# Sheet1.net
KiCad netlist of a schematic drawn in Altium Designer
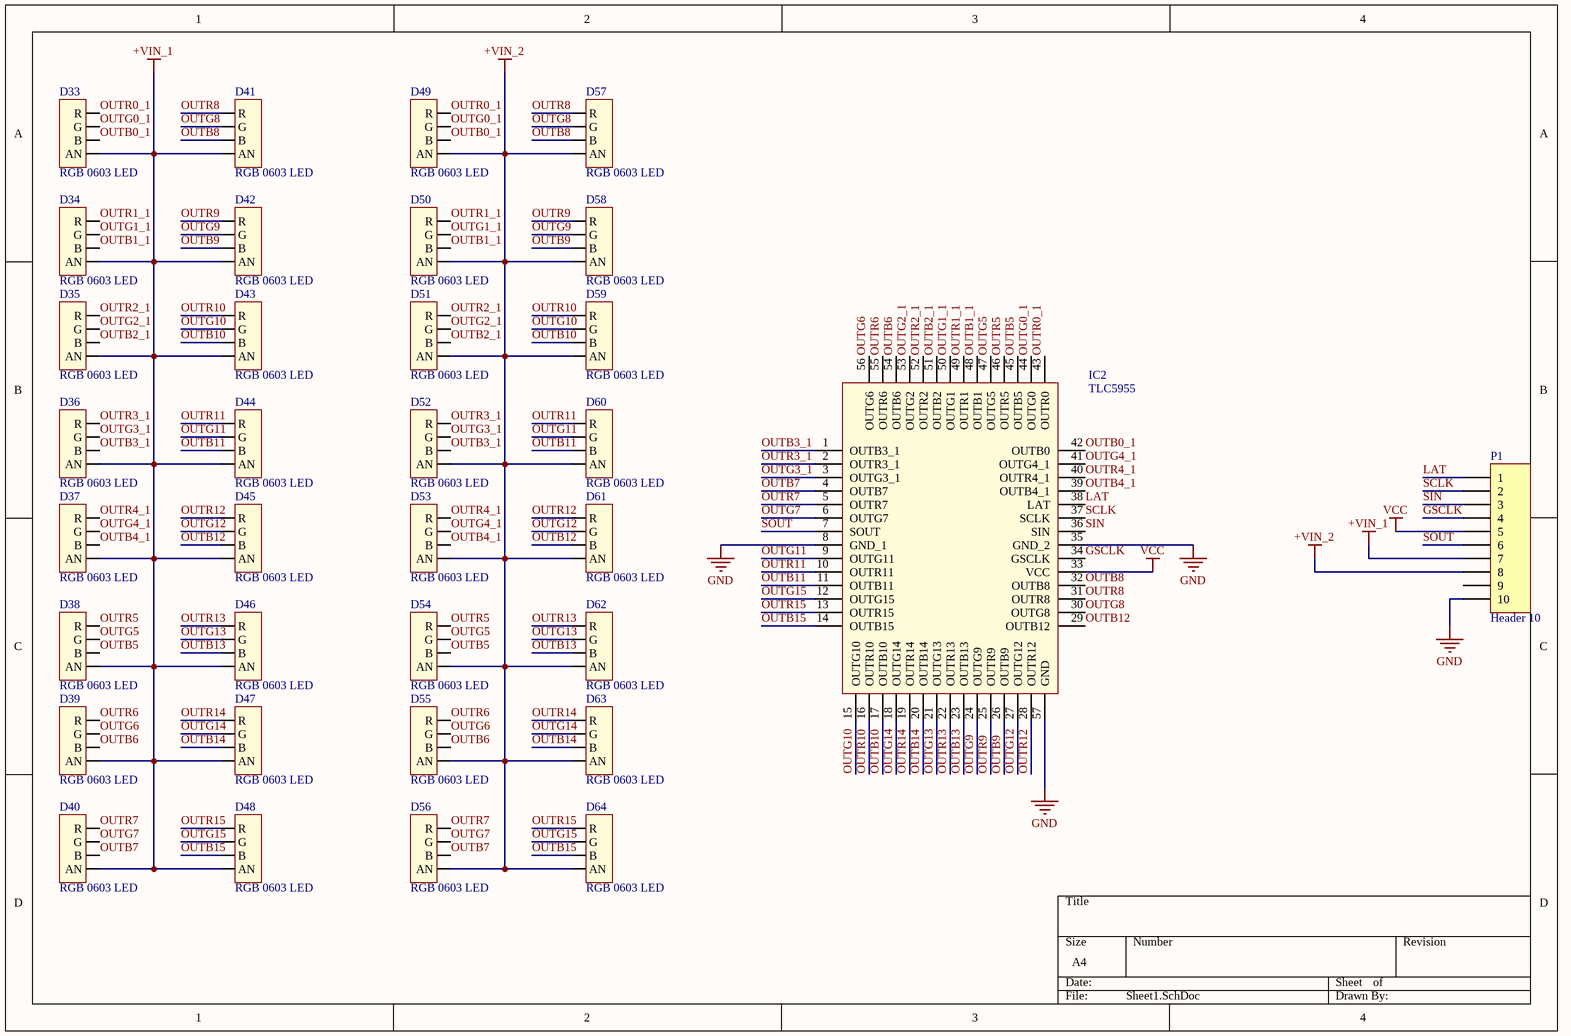
[diagram p0: Sheet1.SchDoc]

(export (version "E")
  (design (tool "Eeschema 10.0.6"))
  (components
    (comp (ref "D33")
      (value "RGB 0603 LED")
      (footprint "RGB LED")
      (libsource (lib "Schlib1") (part "RGB 0603 LED"))
    )
    (comp (ref "D34")
      (value "RGB 0603 LED")
      (footprint "RGB LED")
      (libsource (lib "Schlib1") (part "RGB 0603 LED"))
    )
    (comp (ref "D35")
      (value "RGB 0603 LED")
      (footprint "RGB LED")
      (libsource (lib "Schlib1") (part "RGB 0603 LED"))
    )
    (comp (ref "D36")
      (value "RGB 0603 LED")
      (footprint "RGB LED")
      (libsource (lib "Schlib1") (part "RGB 0603 LED"))
    )
    (comp (ref "D37")
      (value "RGB 0603 LED")
      (footprint "RGB LED")
      (libsource (lib "Schlib1") (part "RGB 0603 LED"))
    )
    (comp (ref "D38")
      (value "RGB 0603 LED")
      (footprint "RGB LED")
      (libsource (lib "Schlib1") (part "RGB 0603 LED"))
    )
    (comp (ref "D39")
      (value "RGB 0603 LED")
      (footprint "RGB LED")
      (libsource (lib "Schlib1") (part "RGB 0603 LED"))
    )
    (comp (ref "D40")
      (value "RGB 0603 LED")
      (footprint "RGB LED")
      (libsource (lib "Schlib1") (part "RGB 0603 LED"))
    )
    (comp (ref "D41")
      (value "RGB 0603 LED")
      (footprint "RGB LED")
      (libsource (lib "") (part "RGB 0603 LED_1"))
    )
    (comp (ref "D42")
      (value "RGB 0603 LED")
      (footprint "RGB LED")
      (libsource (lib "") (part "RGB 0603 LED_1"))
    )
    (comp (ref "D43")
      (value "RGB 0603 LED")
      (footprint "RGB LED")
      (libsource (lib "") (part "RGB 0603 LED_1"))
    )
    (comp (ref "D44")
      (value "RGB 0603 LED")
      (footprint "RGB LED")
      (libsource (lib "") (part "RGB 0603 LED_1"))
    )
    (comp (ref "D45")
      (value "RGB 0603 LED")
      (footprint "RGB LED")
      (libsource (lib "") (part "RGB 0603 LED_1"))
    )
    (comp (ref "D46")
      (value "RGB 0603 LED")
      (footprint "RGB LED")
      (libsource (lib "") (part "RGB 0603 LED_1"))
    )
    (comp (ref "D47")
      (value "RGB 0603 LED")
      (footprint "RGB LED")
      (libsource (lib "") (part "RGB 0603 LED_1"))
    )
    (comp (ref "D48")
      (value "RGB 0603 LED")
      (footprint "RGB LED")
      (libsource (lib "") (part "RGB 0603 LED_1"))
    )
    (comp (ref "D49")
      (value "RGB 0603 LED")
      (footprint "RGB LED")
      (libsource (lib "Schlib1") (part "RGB 0603 LED"))
    )
    (comp (ref "D50")
      (value "RGB 0603 LED")
      (footprint "RGB LED")
      (libsource (lib "Schlib1") (part "RGB 0603 LED"))
    )
    (comp (ref "D51")
      (value "RGB 0603 LED")
      (footprint "RGB LED")
      (libsource (lib "Schlib1") (part "RGB 0603 LED"))
    )
    (comp (ref "D52")
      (value "RGB 0603 LED")
      (footprint "RGB LED")
      (libsource (lib "Schlib1") (part "RGB 0603 LED"))
    )
    (comp (ref "D53")
      (value "RGB 0603 LED")
      (footprint "RGB LED")
      (libsource (lib "Schlib1") (part "RGB 0603 LED"))
    )
    (comp (ref "D54")
      (value "RGB 0603 LED")
      (footprint "RGB LED")
      (libsource (lib "Schlib1") (part "RGB 0603 LED"))
    )
    (comp (ref "D55")
      (value "RGB 0603 LED")
      (footprint "RGB LED")
      (libsource (lib "Schlib1") (part "RGB 0603 LED"))
    )
    (comp (ref "D56")
      (value "RGB 0603 LED")
      (footprint "RGB LED")
      (libsource (lib "Schlib1") (part "RGB 0603 LED"))
    )
    (comp (ref "D57")
      (value "RGB 0603 LED")
      (footprint "RGB LED")
      (libsource (lib "") (part "RGB 0603 LED_1"))
    )
    (comp (ref "D58")
      (value "RGB 0603 LED")
      (footprint "RGB LED")
      (libsource (lib "") (part "RGB 0603 LED_1"))
    )
    (comp (ref "D59")
      (value "RGB 0603 LED")
      (footprint "RGB LED")
      (libsource (lib "") (part "RGB 0603 LED_1"))
    )
    (comp (ref "D60")
      (value "RGB 0603 LED")
      (footprint "RGB LED")
      (libsource (lib "") (part "RGB 0603 LED_1"))
    )
    (comp (ref "D61")
      (value "RGB 0603 LED")
      (footprint "RGB LED")
      (libsource (lib "") (part "RGB 0603 LED_1"))
    )
    (comp (ref "D62")
      (value "RGB 0603 LED")
      (footprint "RGB LED")
      (libsource (lib "") (part "RGB 0603 LED_1"))
    )
    (comp (ref "D63")
      (value "RGB 0603 LED")
      (footprint "RGB LED")
      (libsource (lib "") (part "RGB 0603 LED_1"))
    )
    (comp (ref "D64")
      (value "RGB 0603 LED")
      (footprint "RGB LED")
      (libsource (lib "") (part "RGB 0603 LED_1"))
    )
    (comp (ref "IC2") (value "TLC5955") (footprint "TLC5955") (libsource (lib "Schlib1") (part "TLC5955")))
    (comp (ref "P1")
      (value "Header 10")
      (footprint "HDR1X10")
      (description "Header, 10-Pin")
      (fields (field (name "PUBLISHER") "Altium Limited"))
      (libsource (lib "Miscellaneous Connectors") (part "Header 10"))
    )
  )
  (nets
    (net (code "1") (name "+VIN_1") (class "Default")
      (node (ref "D33") (pin "4") (pinfunction "AN_4") (pintype "passive"))
      (node (ref "D34") (pin "4") (pinfunction "AN_4") (pintype "passive"))
      (node (ref "D35") (pin "4") (pinfunction "AN_4") (pintype "passive"))
      (node (ref "D36") (pin "4") (pinfunction "AN_4") (pintype "passive"))
      (node (ref "D37") (pin "4") (pinfunction "AN_4") (pintype "passive"))
      (node (ref "D38") (pin "4") (pinfunction "AN_4") (pintype "passive"))
      (node (ref "D39") (pin "4") (pinfunction "AN_4") (pintype "passive"))
      (node (ref "D40") (pin "4") (pinfunction "AN_4") (pintype "passive"))
      (node (ref "D41") (pin "4") (pinfunction "AN_4") (pintype "passive"))
      (node (ref "D42") (pin "4") (pinfunction "AN_4") (pintype "passive"))
      (node (ref "D43") (pin "4") (pinfunction "AN_4") (pintype "passive"))
      (node (ref "D44") (pin "4") (pinfunction "AN_4") (pintype "passive"))
      (node (ref "D45") (pin "4") (pinfunction "AN_4") (pintype "passive"))
      (node (ref "D46") (pin "4") (pinfunction "AN_4") (pintype "passive"))
      (node (ref "D47") (pin "4") (pinfunction "AN_4") (pintype "passive"))
      (node (ref "D48") (pin "4") (pinfunction "AN_4") (pintype "passive"))
      (node (ref "P1") (pin "7") (pinfunction "7_7") (pintype "passive"))
    )
    (net (code "2") (name "+VIN_2") (class "Default")
      (node (ref "D49") (pin "4") (pinfunction "AN_4") (pintype "passive"))
      (node (ref "D50") (pin "4") (pinfunction "AN_4") (pintype "passive"))
      (node (ref "D51") (pin "4") (pinfunction "AN_4") (pintype "passive"))
      (node (ref "D52") (pin "4") (pinfunction "AN_4") (pintype "passive"))
      (node (ref "D53") (pin "4") (pinfunction "AN_4") (pintype "passive"))
      (node (ref "D54") (pin "4") (pinfunction "AN_4") (pintype "passive"))
      (node (ref "D55") (pin "4") (pinfunction "AN_4") (pintype "passive"))
      (node (ref "D56") (pin "4") (pinfunction "AN_4") (pintype "passive"))
      (node (ref "D57") (pin "4") (pinfunction "AN_4") (pintype "passive"))
      (node (ref "D58") (pin "4") (pinfunction "AN_4") (pintype "passive"))
      (node (ref "D59") (pin "4") (pinfunction "AN_4") (pintype "passive"))
      (node (ref "D60") (pin "4") (pinfunction "AN_4") (pintype "passive"))
      (node (ref "D61") (pin "4") (pinfunction "AN_4") (pintype "passive"))
      (node (ref "D62") (pin "4") (pinfunction "AN_4") (pintype "passive"))
      (node (ref "D63") (pin "4") (pinfunction "AN_4") (pintype "passive"))
      (node (ref "D64") (pin "4") (pinfunction "AN_4") (pintype "passive"))
      (node (ref "P1") (pin "8") (pinfunction "8_8") (pintype "passive"))
    )
    (net (code "3") (name "/GSCLK") (class "Default")
      (node (ref "IC2") (pin "34") (pinfunction "GSCLK_34") (pintype "passive"))
      (node (ref "P1") (pin "4") (pinfunction "4_4") (pintype "passive"))
    )
    (net (code "4") (name "/LAT") (class "Default")
      (node (ref "IC2") (pin "38") (pinfunction "LAT_38") (pintype "passive"))
      (node (ref "P1") (pin "1") (pinfunction "1_1") (pintype "passive"))
    )
    (net (code "5") (name "/OUTB0_1") (class "Default")
      (node (ref "D33") (pin "3") (pinfunction "B_3") (pintype "passive"))
      (node (ref "D49") (pin "3") (pinfunction "B_3") (pintype "passive"))
      (node (ref "IC2") (pin "42") (pinfunction "OUTB0_42") (pintype "passive"))
    )
    (net (code "6") (name "/OUTB1_1") (class "Default")
      (node (ref "D34") (pin "3") (pinfunction "B_3") (pintype "passive"))
      (node (ref "D50") (pin "3") (pinfunction "B_3") (pintype "passive"))
      (node (ref "IC2") (pin "48") (pinfunction "OUTB1_48") (pintype "passive"))
    )
    (net (code "7") (name "/OUTB2_1") (class "Default")
      (node (ref "D35") (pin "3") (pinfunction "B_3") (pintype "passive"))
      (node (ref "D51") (pin "3") (pinfunction "B_3") (pintype "passive"))
      (node (ref "IC2") (pin "51") (pinfunction "OUTB2_51") (pintype "passive"))
    )
    (net (code "8") (name "/OUTB3_1") (class "Default")
      (node (ref "D36") (pin "3") (pinfunction "B_3") (pintype "passive"))
      (node (ref "D52") (pin "3") (pinfunction "B_3") (pintype "passive"))
      (node (ref "IC2") (pin "1") (pinfunction "OUTB3_1_1") (pintype "passive"))
    )
    (net (code "9") (name "/OUTB4_1") (class "Default")
      (node (ref "D37") (pin "3") (pinfunction "B_3") (pintype "passive"))
      (node (ref "D53") (pin "3") (pinfunction "B_3") (pintype "passive"))
      (node (ref "IC2") (pin "39") (pinfunction "OUTB4_1_39") (pintype "passive"))
    )
    (net (code "10") (name "/OUTB5") (class "Default")
      (node (ref "D38") (pin "3") (pinfunction "B_3") (pintype "passive"))
      (node (ref "D54") (pin "3") (pinfunction "B_3") (pintype "passive"))
      (node (ref "IC2") (pin "45") (pinfunction "OUTB5_45") (pintype "passive"))
    )
    (net (code "11") (name "/OUTB6") (class "Default")
      (node (ref "D39") (pin "3") (pinfunction "B_3") (pintype "passive"))
      (node (ref "D55") (pin "3") (pinfunction "B_3") (pintype "passive"))
      (node (ref "IC2") (pin "54") (pinfunction "OUTB6_54") (pintype "passive"))
    )
    (net (code "12") (name "/OUTB7") (class "Default")
      (node (ref "D40") (pin "3") (pinfunction "B_3") (pintype "passive"))
      (node (ref "D56") (pin "3") (pinfunction "B_3") (pintype "passive"))
      (node (ref "IC2") (pin "4") (pinfunction "OUTB7_4") (pintype "passive"))
    )
    (net (code "13") (name "/OUTB8") (class "Default")
      (node (ref "D41") (pin "3") (pinfunction "B_3") (pintype "passive"))
      (node (ref "D57") (pin "3") (pinfunction "B_3") (pintype "passive"))
      (node (ref "IC2") (pin "32") (pinfunction "OUTB8_32") (pintype "passive"))
    )
    (net (code "14") (name "/OUTB9") (class "Default")
      (node (ref "D42") (pin "3") (pinfunction "B_3") (pintype "passive"))
      (node (ref "D58") (pin "3") (pinfunction "B_3") (pintype "passive"))
      (node (ref "IC2") (pin "26") (pinfunction "OUTB9_26") (pintype "passive"))
    )
    (net (code "15") (name "/OUTB10") (class "Default")
      (node (ref "D43") (pin "3") (pinfunction "B_3") (pintype "passive"))
      (node (ref "D59") (pin "3") (pinfunction "B_3") (pintype "passive"))
      (node (ref "IC2") (pin "17") (pinfunction "OUTB10_17") (pintype "passive"))
    )
    (net (code "16") (name "/OUTB11") (class "Default")
      (node (ref "D44") (pin "3") (pinfunction "B_3") (pintype "passive"))
      (node (ref "D60") (pin "3") (pinfunction "B_3") (pintype "passive"))
      (node (ref "IC2") (pin "11") (pinfunction "OUTB11_11") (pintype "passive"))
    )
    (net (code "17") (name "/OUTB12") (class "Default")
      (node (ref "D45") (pin "3") (pinfunction "B_3") (pintype "passive"))
      (node (ref "D61") (pin "3") (pinfunction "B_3") (pintype "passive"))
      (node (ref "IC2") (pin "29") (pinfunction "OUTB12_29") (pintype "passive"))
    )
    (net (code "18") (name "/OUTB13") (class "Default")
      (node (ref "D46") (pin "3") (pinfunction "B_3") (pintype "passive"))
      (node (ref "D62") (pin "3") (pinfunction "B_3") (pintype "passive"))
      (node (ref "IC2") (pin "23") (pinfunction "OUTB13_23") (pintype "passive"))
    )
    (net (code "19") (name "/OUTB14") (class "Default")
      (node (ref "D47") (pin "3") (pinfunction "B_3") (pintype "passive"))
      (node (ref "D63") (pin "3") (pinfunction "B_3") (pintype "passive"))
      (node (ref "IC2") (pin "20") (pinfunction "OUTB14_20") (pintype "passive"))
    )
    (net (code "20") (name "/OUTB15") (class "Default")
      (node (ref "D48") (pin "3") (pinfunction "B_3") (pintype "passive"))
      (node (ref "D64") (pin "3") (pinfunction "B_3") (pintype "passive"))
      (node (ref "IC2") (pin "14") (pinfunction "OUTB15_14") (pintype "passive"))
    )
    (net (code "21") (name "/OUTG0_1") (class "Default")
      (node (ref "D33") (pin "2") (pinfunction "G_2") (pintype "passive"))
      (node (ref "D49") (pin "2") (pinfunction "G_2") (pintype "passive"))
      (node (ref "IC2") (pin "44") (pinfunction "OUTG0_44") (pintype "passive"))
    )
    (net (code "22") (name "/OUTG1_1") (class "Default")
      (node (ref "D34") (pin "2") (pinfunction "G_2") (pintype "passive"))
      (node (ref "D50") (pin "2") (pinfunction "G_2") (pintype "passive"))
      (node (ref "IC2") (pin "50") (pinfunction "OUTG1_50") (pintype "passive"))
    )
    (net (code "23") (name "/OUTG2_1") (class "Default")
      (node (ref "D35") (pin "2") (pinfunction "G_2") (pintype "passive"))
      (node (ref "D51") (pin "2") (pinfunction "G_2") (pintype "passive"))
      (node (ref "IC2") (pin "53") (pinfunction "OUTG2_53") (pintype "passive"))
    )
    (net (code "24") (name "/OUTG3_1") (class "Default")
      (node (ref "D36") (pin "2") (pinfunction "G_2") (pintype "passive"))
      (node (ref "D52") (pin "2") (pinfunction "G_2") (pintype "passive"))
      (node (ref "IC2") (pin "3") (pinfunction "OUTG3_1_3") (pintype "passive"))
    )
    (net (code "25") (name "/OUTG4_1") (class "Default")
      (node (ref "D37") (pin "2") (pinfunction "G_2") (pintype "passive"))
      (node (ref "D53") (pin "2") (pinfunction "G_2") (pintype "passive"))
      (node (ref "IC2") (pin "41") (pinfunction "OUTG4_1_41") (pintype "passive"))
    )
    (net (code "26") (name "/OUTG5") (class "Default")
      (node (ref "D38") (pin "2") (pinfunction "G_2") (pintype "passive"))
      (node (ref "D54") (pin "2") (pinfunction "G_2") (pintype "passive"))
      (node (ref "IC2") (pin "47") (pinfunction "OUTG5_47") (pintype "passive"))
    )
    (net (code "27") (name "/OUTG6") (class "Default")
      (node (ref "D39") (pin "2") (pinfunction "G_2") (pintype "passive"))
      (node (ref "D55") (pin "2") (pinfunction "G_2") (pintype "passive"))
      (node (ref "IC2") (pin "56") (pinfunction "OUTG6_56") (pintype "passive"))
    )
    (net (code "28") (name "/OUTG7") (class "Default")
      (node (ref "D40") (pin "2") (pinfunction "G_2") (pintype "passive"))
      (node (ref "D56") (pin "2") (pinfunction "G_2") (pintype "passive"))
      (node (ref "IC2") (pin "6") (pinfunction "OUTG7_6") (pintype "passive"))
    )
    (net (code "29") (name "/OUTG8") (class "Default")
      (node (ref "D41") (pin "2") (pinfunction "G_2") (pintype "passive"))
      (node (ref "D57") (pin "2") (pinfunction "G_2") (pintype "passive"))
      (node (ref "IC2") (pin "30") (pinfunction "OUTG8_30") (pintype "passive"))
    )
    (net (code "30") (name "/OUTG9") (class "Default")
      (node (ref "D42") (pin "2") (pinfunction "G_2") (pintype "passive"))
      (node (ref "D58") (pin "2") (pinfunction "G_2") (pintype "passive"))
      (node (ref "IC2") (pin "24") (pinfunction "OUTG9_24") (pintype "passive"))
    )
    (net (code "31") (name "/OUTG10") (class "Default")
      (node (ref "D43") (pin "2") (pinfunction "G_2") (pintype "passive"))
      (node (ref "D59") (pin "2") (pinfunction "G_2") (pintype "passive"))
      (node (ref "IC2") (pin "15") (pinfunction "OUTG10_15") (pintype "passive"))
    )
    (net (code "32") (name "/OUTG11") (class "Default")
      (node (ref "D44") (pin "2") (pinfunction "G_2") (pintype "passive"))
      (node (ref "D60") (pin "2") (pinfunction "G_2") (pintype "passive"))
      (node (ref "IC2") (pin "9") (pinfunction "OUTG11_9") (pintype "passive"))
    )
    (net (code "33") (name "/OUTG12") (class "Default")
      (node (ref "D45") (pin "2") (pinfunction "G_2") (pintype "passive"))
      (node (ref "D61") (pin "2") (pinfunction "G_2") (pintype "passive"))
      (node (ref "IC2") (pin "27") (pinfunction "OUTG12_27") (pintype "passive"))
    )
    (net (code "34") (name "/OUTG13") (class "Default")
      (node (ref "D46") (pin "2") (pinfunction "G_2") (pintype "passive"))
      (node (ref "D62") (pin "2") (pinfunction "G_2") (pintype "passive"))
      (node (ref "IC2") (pin "21") (pinfunction "OUTG13_21") (pintype "passive"))
    )
    (net (code "35") (name "/OUTG14") (class "Default")
      (node (ref "D47") (pin "2") (pinfunction "G_2") (pintype "passive"))
      (node (ref "D63") (pin "2") (pinfunction "G_2") (pintype "passive"))
      (node (ref "IC2") (pin "18") (pinfunction "OUTG14_18") (pintype "passive"))
    )
    (net (code "36") (name "/OUTG15") (class "Default")
      (node (ref "D48") (pin "2") (pinfunction "G_2") (pintype "passive"))
      (node (ref "D64") (pin "2") (pinfunction "G_2") (pintype "passive"))
      (node (ref "IC2") (pin "12") (pinfunction "OUTG15_12") (pintype "passive"))
    )
    (net (code "37") (name "/OUTR0_1") (class "Default")
      (node (ref "D33") (pin "1") (pinfunction "R_1") (pintype "passive"))
      (node (ref "D49") (pin "1") (pinfunction "R_1") (pintype "passive"))
      (node (ref "IC2") (pin "43") (pinfunction "OUTR0_43") (pintype "passive"))
    )
    (net (code "38") (name "/OUTR1_1") (class "Default")
      (node (ref "D34") (pin "1") (pinfunction "R_1") (pintype "passive"))
      (node (ref "D50") (pin "1") (pinfunction "R_1") (pintype "passive"))
      (node (ref "IC2") (pin "49") (pinfunction "OUTR1_49") (pintype "passive"))
    )
    (net (code "39") (name "/OUTR2_1") (class "Default")
      (node (ref "D35") (pin "1") (pinfunction "R_1") (pintype "passive"))
      (node (ref "D51") (pin "1") (pinfunction "R_1") (pintype "passive"))
      (node (ref "IC2") (pin "52") (pinfunction "OUTR2_52") (pintype "passive"))
    )
    (net (code "40") (name "/OUTR3_1") (class "Default")
      (node (ref "D36") (pin "1") (pinfunction "R_1") (pintype "passive"))
      (node (ref "D52") (pin "1") (pinfunction "R_1") (pintype "passive"))
      (node (ref "IC2") (pin "2") (pinfunction "OUTR3_1_2") (pintype "passive"))
    )
    (net (code "41") (name "/OUTR4_1") (class "Default")
      (node (ref "D37") (pin "1") (pinfunction "R_1") (pintype "passive"))
      (node (ref "D53") (pin "1") (pinfunction "R_1") (pintype "passive"))
      (node (ref "IC2") (pin "40") (pinfunction "OUTR4_1_40") (pintype "passive"))
    )
    (net (code "42") (name "/OUTR5") (class "Default")
      (node (ref "D38") (pin "1") (pinfunction "R_1") (pintype "passive"))
      (node (ref "D54") (pin "1") (pinfunction "R_1") (pintype "passive"))
      (node (ref "IC2") (pin "46") (pinfunction "OUTR5_46") (pintype "passive"))
    )
    (net (code "43") (name "/OUTR6") (class "Default")
      (node (ref "D39") (pin "1") (pinfunction "R_1") (pintype "passive"))
      (node (ref "D55") (pin "1") (pinfunction "R_1") (pintype "passive"))
      (node (ref "IC2") (pin "55") (pinfunction "OUTR6_55") (pintype "passive"))
    )
    (net (code "44") (name "/OUTR7") (class "Default")
      (node (ref "D40") (pin "1") (pinfunction "R_1") (pintype "passive"))
      (node (ref "D56") (pin "1") (pinfunction "R_1") (pintype "passive"))
      (node (ref "IC2") (pin "5") (pinfunction "OUTR7_5") (pintype "passive"))
    )
    (net (code "45") (name "/OUTR8") (class "Default")
      (node (ref "D41") (pin "1") (pinfunction "R_1") (pintype "passive"))
      (node (ref "D57") (pin "1") (pinfunction "R_1") (pintype "passive"))
      (node (ref "IC2") (pin "31") (pinfunction "OUTR8_31") (pintype "passive"))
    )
    (net (code "46") (name "/OUTR9") (class "Default")
      (node (ref "D42") (pin "1") (pinfunction "R_1") (pintype "passive"))
      (node (ref "D58") (pin "1") (pinfunction "R_1") (pintype "passive"))
      (node (ref "IC2") (pin "25") (pinfunction "OUTR9_25") (pintype "passive"))
    )
    (net (code "47") (name "/OUTR10") (class "Default")
      (node (ref "D43") (pin "1") (pinfunction "R_1") (pintype "passive"))
      (node (ref "D59") (pin "1") (pinfunction "R_1") (pintype "passive"))
      (node (ref "IC2") (pin "16") (pinfunction "OUTR10_16") (pintype "passive"))
    )
    (net (code "48") (name "/OUTR11") (class "Default")
      (node (ref "D44") (pin "1") (pinfunction "R_1") (pintype "passive"))
      (node (ref "D60") (pin "1") (pinfunction "R_1") (pintype "passive"))
      (node (ref "IC2") (pin "10") (pinfunction "OUTR11_10") (pintype "passive"))
    )
    (net (code "49") (name "/OUTR12") (class "Default")
      (node (ref "D45") (pin "1") (pinfunction "R_1") (pintype "passive"))
      (node (ref "D61") (pin "1") (pinfunction "R_1") (pintype "passive"))
      (node (ref "IC2") (pin "28") (pinfunction "OUTR12_28") (pintype "passive"))
    )
    (net (code "50") (name "/OUTR13") (class "Default")
      (node (ref "D46") (pin "1") (pinfunction "R_1") (pintype "passive"))
      (node (ref "D62") (pin "1") (pinfunction "R_1") (pintype "passive"))
      (node (ref "IC2") (pin "22") (pinfunction "OUTR13_22") (pintype "passive"))
    )
    (net (code "51") (name "/OUTR14") (class "Default")
      (node (ref "D47") (pin "1") (pinfunction "R_1") (pintype "passive"))
      (node (ref "D63") (pin "1") (pinfunction "R_1") (pintype "passive"))
      (node (ref "IC2") (pin "19") (pinfunction "OUTR14_19") (pintype "passive"))
    )
    (net (code "52") (name "/OUTR15") (class "Default")
      (node (ref "D48") (pin "1") (pinfunction "R_1") (pintype "passive"))
      (node (ref "D64") (pin "1") (pinfunction "R_1") (pintype "passive"))
      (node (ref "IC2") (pin "13") (pinfunction "OUTR15_13") (pintype "passive"))
    )
    (net (code "53") (name "/SCLK") (class "Default")
      (node (ref "IC2") (pin "37") (pinfunction "SCLK_37") (pintype "passive"))
      (node (ref "P1") (pin "2") (pinfunction "2_2") (pintype "passive"))
    )
    (net (code "54") (name "/SIN") (class "Default")
      (node (ref "IC2") (pin "36") (pinfunction "SIN_36") (pintype "passive"))
      (node (ref "P1") (pin "3") (pinfunction "3_3") (pintype "passive"))
    )
    (net (code "55") (name "/SOUT") (class "Default")
      (node (ref "IC2") (pin "7") (pinfunction "SOUT_7") (pintype "passive"))
      (node (ref "P1") (pin "6") (pinfunction "6_6") (pintype "passive"))
    )
    (net (code "56") (name "GND") (class "Default")
      (node (ref "IC2") (pin "35") (pinfunction "GND_2_35") (pintype "passive"))
      (node (ref "IC2") (pin "57") (pinfunction "GND_57") (pintype "passive"))
      (node (ref "IC2") (pin "8") (pinfunction "GND_1_8") (pintype "passive"))
      (node (ref "P1") (pin "10") (pinfunction "10_10") (pintype "passive"))
    )
    (net (code "57") (name "VCC") (class "Default")
      (node (ref "IC2") (pin "33") (pinfunction "VCC_33") (pintype "passive"))
      (node (ref "P1") (pin "5") (pinfunction "5_5") (pintype "passive"))
    )
    (net (code "58") (name "unconnected-(P1-Pad9)") (class "Default")
      (node (ref "P1") (pin "9") (pinfunction "9_9") (pintype "passive"))
    )
  )
)
